# LTC6803.net
KiCad netlist of a schematic drawn in Altium Designer
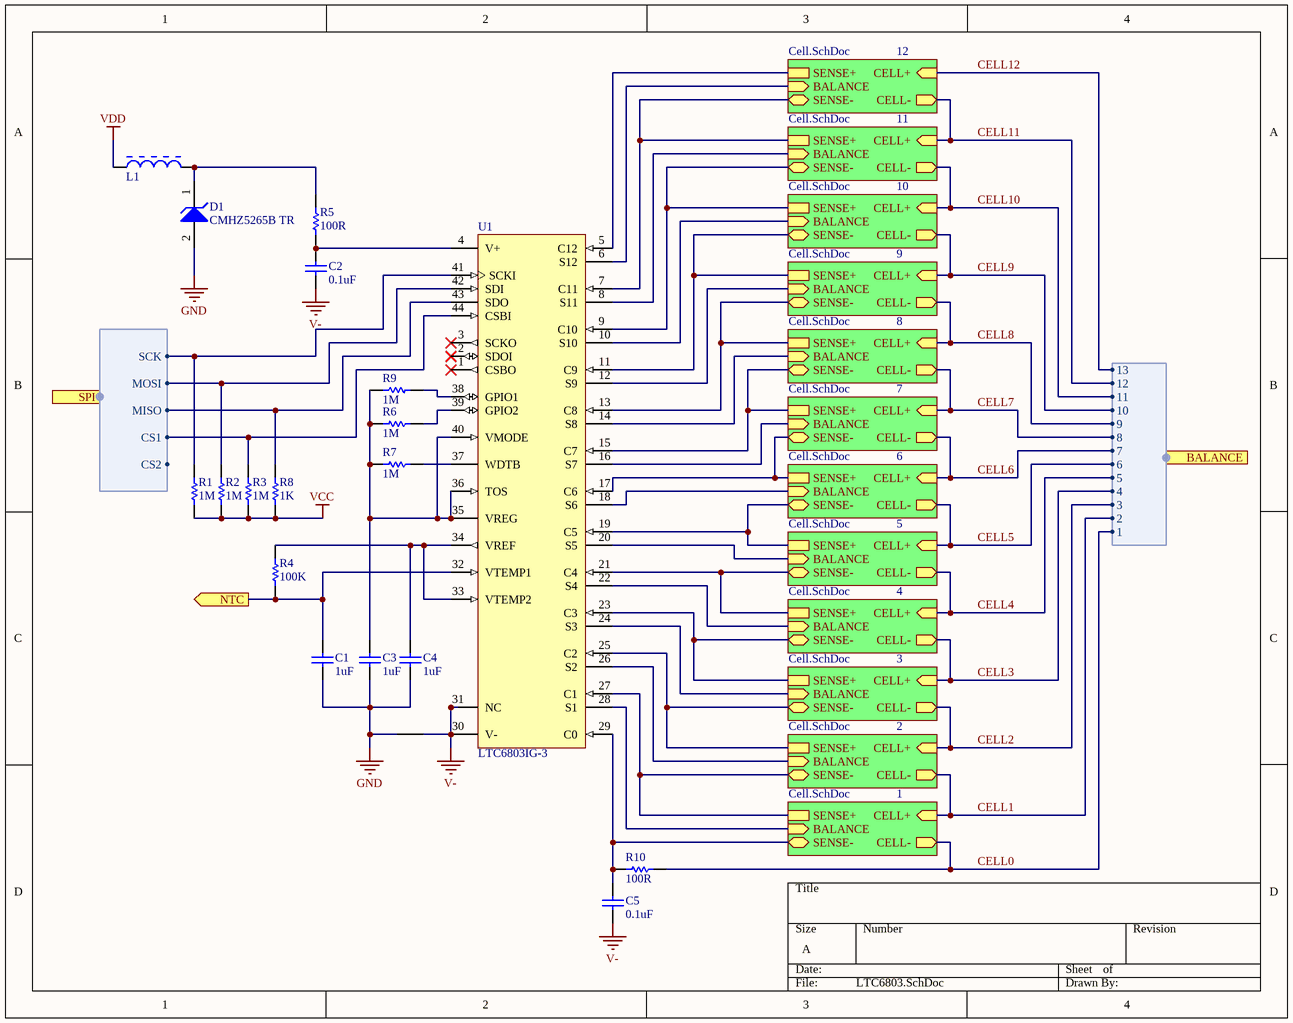
[diagram p0: LTC6803.SchDoc]

(export (version "E")
  (design (tool "Eeschema 10.0.6"))
  (components
    (comp (ref "*") (value "NetTie") (footprint "NetTie") (libsource (lib "Components") (part "NetTie")))
    (comp (ref "C1")
      (value "1uF")
      (footprint "C0603[1608X92]")
      (description "1uF 6.3V 10% 0603 (1608 Metric)")
      (fields (field (name "PARTNUMBER") "GRM188R60J105KA01D") (field (name "MANUFACTURER") "Murata"))
      (libsource (lib "Capacitors") (part "CAP_1uF_6.3V_0603_10%"))
    )
    (comp (ref "C2")
      (value "0.1uF")
      (footprint "C0603[1608X92]")
      (description "0.1uF 100V 10% 0603 (1608 Metric)")
      (fields (field (name "PARTNUMBER") "GRM188R72A104KA35D") (field (name "MANUFACTURER") "Murata"))
      (libsource (lib "Capacitors") (part "CAP_0.1uF_100V_0603_10%"))
    )
    (comp (ref "C3")
      (value "1uF")
      (footprint "C0603[1608X92]")
      (description "1uF 6.3V 10% 0603 (1608 Metric)")
      (fields (field (name "PARTNUMBER") "GRM188R60J105KA01D") (field (name "MANUFACTURER") "Murata"))
      (libsource (lib "Capacitors") (part "CAP_1uF_6.3V_0603_10%"))
    )
    (comp (ref "C4")
      (value "1uF")
      (footprint "C0603[1608X92]")
      (description "1uF 6.3V 10% 0603 (1608 Metric)")
      (fields (field (name "PARTNUMBER") "GRM188R60J105KA01D") (field (name "MANUFACTURER") "Murata"))
      (libsource (lib "Capacitors") (part "CAP_1uF_6.3V_0603_10%"))
    )
    (comp (ref "C5")
      (value "0.1uF")
      (footprint "C0603[1608X92]")
      (description "0.1uF 6.3V 10% 0603 (1608 Metric)")
      (fields (field (name "PARTNUMBER") "GRM188R70J104KA01D") (field (name "MANUFACTURER") "Murata"))
      (libsource (lib "Capacitors") (part "CAP_0.1uF_6.3V_0603_10%"))
    )
    (comp (ref "D1")
      (value "CMHZ5265B TR")
      (footprint "SOD-123")
      (description "Zener Diodes 500mW Zener Diode 185mA 58.9V to 2V")
      (fields (field (name "PARTNUMBER") "CMHZ5265B") (field (name "MANUFACTURER") "Central Semiconductor"))
      (libsource (lib "Diodes") (part "CMHZ5265B"))
    )
    (comp (ref "L1")
      (value "MURA-FB-2")
      (footprint "MURA-BLM31-B60-CHIP-2_V3")
      (description "EMI Filter Beads, Chips & Arrays 1206 33 OHM")
      (fields (field (name "PARTNUMBER") "BLM31PG330SN1L") (field (name "MANUFACTURER") "Murata"))
      (libsource (lib "Components") (part "MURA-FB-2"))
    )
    (comp (ref "R1")
      (value "1M")
      (footprint "R0603[1608]")
      (description "1M 0.25W 1% 0603 (1005 Metric)")
      (fields (field (name "MANUFACTURER") "Vishay / Dale") (field (name "PARTNUMBER") "CRCW06031M00JNEAHP"))
      (libsource (lib "Resistors") (part "RES_1M_0603_1%"))
    )
    (comp (ref "R2")
      (value "1M")
      (footprint "R0603[1608]")
      (description "1M 0.25W 1% 0603 (1005 Metric)")
      (fields (field (name "MANUFACTURER") "Vishay / Dale") (field (name "PARTNUMBER") "CRCW06031M00JNEAHP"))
      (libsource (lib "Resistors") (part "RES_1M_0603_1%"))
    )
    (comp (ref "R3")
      (value "1M")
      (footprint "R0603[1608]")
      (description "1M 0.25W 1% 0603 (1005 Metric)")
      (fields (field (name "MANUFACTURER") "Vishay / Dale") (field (name "PARTNUMBER") "CRCW06031M00JNEAHP"))
      (libsource (lib "Resistors") (part "RES_1M_0603_1%"))
    )
    (comp (ref "R4")
      (value "100K")
      (footprint "R0603[1608]")
      (description "100K 0.25W 1% 0603 (1005 Metric)")
      (fields (field (name "MANUFACTURER") "Vishay / Dale") (field (name "PARTNUMBER") "CRCW0603100KFKEAHP"))
      (libsource (lib "Resistors") (part "RES_100K_0603_1%"))
    )
    (comp (ref "R5")
      (value "100R")
      (footprint "R0603[1608]")
      (description "100R 0.25W 1% 0603 (1005 Metric)")
      (fields (field (name "MANUFACTURER") "Vishay / Dale") (field (name "PARTNUMBER") "CRCW0603100RFKEAHP"))
      (libsource (lib "Resistors") (part "RES_100R_0603_1%"))
    )
    (comp (ref "R6")
      (value "1M")
      (footprint "R0603[1608]")
      (description "1M 0.25W 1% 0603 (1005 Metric)")
      (fields (field (name "MANUFACTURER") "Vishay / Dale") (field (name "PARTNUMBER") "CRCW06031M00JNEAHP"))
      (libsource (lib "Resistors") (part "RES_1M_0603_1%"))
    )
    (comp (ref "R7")
      (value "1M")
      (footprint "R0603[1608]")
      (description "1M 0.25W 1% 0603 (1005 Metric)")
      (fields (field (name "MANUFACTURER") "Vishay / Dale") (field (name "PARTNUMBER") "CRCW06031M00JNEAHP"))
      (libsource (lib "Resistors") (part "RES_1M_0603_1%"))
    )
    (comp (ref "R8")
      (value "1K")
      (footprint "R0603[1608]")
      (description "1K 0.25W 1% 0603 (1005 Metric)")
      (fields (field (name "MANUFACTURER") "Vishay / Dale") (field (name "PARTNUMBER") "CRCW06031K00FKEAHP"))
      (libsource (lib "Resistors") (part "RES_1K_0603_1%"))
    )
    (comp (ref "R9")
      (value "1M")
      (footprint "R0603[1608]")
      (description "1M 0.25W 1% 0603 (1005 Metric)")
      (fields (field (name "MANUFACTURER") "Vishay / Dale") (field (name "PARTNUMBER") "CRCW06031M00JNEAHP"))
      (libsource (lib "Resistors") (part "RES_1M_0603_1%"))
    )
    (comp (ref "R10")
      (value "100R")
      (footprint "R0603[1608]")
      (description "100R 0.25W 1% 0603 (1005 Metric)")
      (fields (field (name "MANUFACTURER") "Vishay / Dale") (field (name "PARTNUMBER") "CRCW0603100RFKEAHP"))
      (libsource (lib "Resistors") (part "RES_100R_0603_1%"))
    )
    (comp (ref "U1")
      (value "LTC6803IG-3")
      (footprint "TSSOP-44")
      (fields (field (name "PARTNUMBER") "LTC6803IG-3#PBF") (field (name "MANUFACTURER") "Linear Technology"))
      (libsource (lib "ICs") (part "LTC6803IG-3"))
    )
  )
  (nets
    (net (code "3") (name "/BALANCE") (class "Default")
      (node (ref "U1") (pin "28") (pinfunction "S1_28") (pintype "tri_state"))
    )
    (net (code "4") (name "/BALANCE_1") (class "Default")
      (node (ref "U1") (pin "10") (pinfunction "S10_10") (pintype "tri_state"))
    )
    (net (code "5") (name "/BALANCE_2") (class "Default")
      (node (ref "U1") (pin "6") (pinfunction "S12_6") (pintype "tri_state"))
    )
    (net (code "6") (name "/BALANCE_3") (class "Default")
      (node (ref "U1") (pin "8") (pinfunction "S11_8") (pintype "tri_state"))
    )
    (net (code "7") (name "/BALANCE_4") (class "Default")
      (node (ref "U1") (pin "12") (pinfunction "S9_12") (pintype "tri_state"))
    )
    (net (code "8") (name "/BALANCE_5") (class "Default")
      (node (ref "U1") (pin "14") (pinfunction "S8_14") (pintype "tri_state"))
    )
    (net (code "9") (name "/BALANCE_6") (class "Default")
      (node (ref "U1") (pin "16") (pinfunction "S7_16") (pintype "tri_state"))
    )
    (net (code "10") (name "/BALANCE_7") (class "Default")
      (node (ref "U1") (pin "18") (pinfunction "S6_18") (pintype "tri_state"))
    )
    (net (code "11") (name "/BALANCE_8") (class "Default")
      (node (ref "U1") (pin "20") (pinfunction "S5_20") (pintype "tri_state"))
    )
    (net (code "12") (name "/BALANCE_9") (class "Default")
      (node (ref "U1") (pin "22") (pinfunction "S4_22") (pintype "tri_state"))
    )
    (net (code "13") (name "/BALANCE_10") (class "Default")
      (node (ref "U1") (pin "24") (pinfunction "S3_24") (pintype "tri_state"))
    )
    (net (code "14") (name "/BALANCE_11") (class "Default")
      (node (ref "U1") (pin "26") (pinfunction "S2_26") (pintype "tri_state"))
    )
    (net (code "15") (name "/CELL0") (class "Default")
      (node (ref "R10") (pin "1") (pinfunction "1_1") (pintype "passive"))
    )
    (net (code "28") (name "/NTC") (class "Default")
      (node (ref "C1") (pin "2") (pinfunction "2_2") (pintype "passive"))
      (node (ref "R4") (pin "1") (pinfunction "1_1") (pintype "passive"))
      (node (ref "U1") (pin "32") (pinfunction "VTEMP1_32") (pintype "input"))
    )
    (net (code "29") (name "/SENSE+") (class "Default")
      (node (ref "U1") (pin "27") (pinfunction "C1_27") (pintype "input"))
    )
    (net (code "30") (name "/SENSE+_1") (class "Default")
      (node (ref "U1") (pin "9") (pinfunction "C10_9") (pintype "input"))
    )
    (net (code "31") (name "/SENSE+_2") (class "Default")
      (node (ref "U1") (pin "11") (pinfunction "C9_11") (pintype "input"))
    )
    (net (code "32") (name "/SENSE+_3") (class "Default")
      (node (ref "U1") (pin "13") (pinfunction "C8_13") (pintype "input"))
    )
    (net (code "33") (name "/SENSE+_4") (class "Default")
      (node (ref "U1") (pin "7") (pinfunction "C11_7") (pintype "input"))
    )
    (net (code "34") (name "/SENSE+_5") (class "Default")
      (node (ref "U1") (pin "5") (pinfunction "C12_5") (pintype "input"))
    )
    (net (code "35") (name "/SENSE+_6") (class "Default")
      (node (ref "U1") (pin "15") (pinfunction "C7_15") (pintype "input"))
    )
    (net (code "36") (name "/SENSE+_7") (class "Default")
      (node (ref "U1") (pin "17") (pinfunction "C6_17") (pintype "input"))
    )
    (net (code "37") (name "/SENSE+_8") (class "Default")
      (node (ref "U1") (pin "19") (pinfunction "C5_19") (pintype "input"))
    )
    (net (code "38") (name "/SENSE+_9") (class "Default")
      (node (ref "U1") (pin "21") (pinfunction "C4_21") (pintype "input"))
    )
    (net (code "39") (name "/SENSE+_10") (class "Default")
      (node (ref "U1") (pin "23") (pinfunction "C3_23") (pintype "input"))
    )
    (net (code "40") (name "/SENSE+_11") (class "Default")
      (node (ref "U1") (pin "25") (pinfunction "C2_25") (pintype "input"))
    )
    (net (code "41") (name "/SENSE-") (class "Default")
      (node (ref "C5") (pin "2") (pinfunction "2_2") (pintype "passive"))
      (node (ref "R10") (pin "2") (pinfunction "2_2") (pintype "passive"))
      (node (ref "U1") (pin "29") (pinfunction "C0_29") (pintype "input"))
    )
    (net (code "44") (name "GND") (class "Default")
      (node (ref "*") (pin "1") (pinfunction "1_1") (pintype "passive"))
      (node (ref "C1") (pin "1") (pinfunction "1_1") (pintype "passive"))
      (node (ref "C3") (pin "1") (pinfunction "1_1") (pintype "passive"))
      (node (ref "C4") (pin "1") (pinfunction "1_1") (pintype "passive"))
      (node (ref "D1") (pin "2") (pinfunction "A_2") (pintype "passive"))
    )
    (net (code "45") (name "Net-(D1-K)") (class "Default")
      (node (ref "D1") (pin "1") (pinfunction "K_1") (pintype "passive"))
      (node (ref "L1") (pin "2") (pinfunction "2_2") (pintype "passive"))
      (node (ref "R5") (pin "2") (pinfunction "2_2") (pintype "passive"))
    )
    (net (code "46") (name "Net-(U1-CSBI)") (class "Default")
      (node (ref "R3") (pin "2") (pinfunction "2_2") (pintype "passive"))
      (node (ref "U1") (pin "44") (pinfunction "CSBI_44") (pintype "input"))
    )
    (net (code "47") (name "Net-(U1-GPIO1)") (class "Default")
      (node (ref "R9") (pin "1") (pinfunction "1_1") (pintype "passive"))
      (node (ref "U1") (pin "38") (pinfunction "GPIO1_38") (pintype "bidirectional"))
    )
    (net (code "48") (name "Net-(U1-GPIO2)") (class "Default")
      (node (ref "R6") (pin "1") (pinfunction "1_1") (pintype "passive"))
      (node (ref "U1") (pin "39") (pinfunction "GPIO2_39") (pintype "bidirectional"))
    )
    (net (code "49") (name "Net-(U1-SCKI)") (class "Default")
      (node (ref "R1") (pin "2") (pinfunction "2_2") (pintype "passive"))
      (node (ref "U1") (pin "41") (pinfunction "SCKI_41") (pintype "input"))
    )
    (net (code "50") (name "Net-(U1-SDI)") (class "Default")
      (node (ref "R2") (pin "2") (pinfunction "2_2") (pintype "passive"))
      (node (ref "U1") (pin "42") (pinfunction "SDI_42") (pintype "input"))
    )
    (net (code "51") (name "Net-(U1-SDO)") (class "Default")
      (node (ref "R8") (pin "2") (pinfunction "2_2") (pintype "passive"))
      (node (ref "U1") (pin "43") (pinfunction "SDO_43") (pintype "open_collector"))
    )
    (net (code "52") (name "Net-(U1-TOS)") (class "Default")
      (node (ref "C3") (pin "2") (pinfunction "2_2") (pintype "passive"))
      (node (ref "R6") (pin "2") (pinfunction "2_2") (pintype "passive"))
      (node (ref "R7") (pin "2") (pinfunction "2_2") (pintype "passive"))
      (node (ref "R9") (pin "2") (pinfunction "2_2") (pintype "passive"))
      (node (ref "U1") (pin "35") (pinfunction "VREG_35") (pintype "power_in"))
      (node (ref "U1") (pin "36") (pinfunction "TOS_36") (pintype "input"))
      (node (ref "U1") (pin "40") (pinfunction "VMODE_40") (pintype "input"))
    )
    (net (code "53") (name "Net-(U1-V+)") (class "Default")
      (node (ref "C2") (pin "2") (pinfunction "2_2") (pintype "passive"))
      (node (ref "R5") (pin "1") (pinfunction "1_1") (pintype "passive"))
      (node (ref "U1") (pin "4") (pinfunction "V+_4") (pintype "power_in"))
    )
    (net (code "54") (name "Net-(U1-VREF)") (class "Default")
      (node (ref "C4") (pin "2") (pinfunction "2_2") (pintype "passive"))
      (node (ref "R4") (pin "2") (pinfunction "2_2") (pintype "passive"))
      (node (ref "U1") (pin "33") (pinfunction "VTEMP2_33") (pintype "input"))
      (node (ref "U1") (pin "34") (pinfunction "VREF_34") (pintype "output"))
    )
    (net (code "55") (name "Net-(U1-WDTB)") (class "Default")
      (node (ref "R7") (pin "1") (pinfunction "1_1") (pintype "passive"))
      (node (ref "U1") (pin "37") (pinfunction "WDTB_37") (pintype "open_collector"))
    )
    (net (code "56") (name "V-") (class "Default")
      (node (ref "*") (pin "2") (pinfunction "2_2") (pintype "passive"))
      (node (ref "C2") (pin "1") (pinfunction "1_1") (pintype "passive"))
      (node (ref "C5") (pin "1") (pinfunction "1_1") (pintype "passive"))
      (node (ref "U1") (pin "30") (pinfunction "V-_30") (pintype "power_in"))
      (node (ref "U1") (pin "31") (pinfunction "NC_31") (pintype "passive"))
    )
    (net (code "57") (name "VCC") (class "Default")
      (node (ref "R1") (pin "1") (pinfunction "1_1") (pintype "passive"))
      (node (ref "R2") (pin "1") (pinfunction "1_1") (pintype "passive"))
      (node (ref "R3") (pin "1") (pinfunction "1_1") (pintype "passive"))
      (node (ref "R8") (pin "1") (pinfunction "1_1") (pintype "passive"))
    )
    (net (code "58") (name "VDD") (class "Default")
      (node (ref "L1") (pin "1") (pinfunction "1_1") (pintype "passive"))
    )
    (net (code "59") (name "unconnected-(U1-CSBO-Pad1)") (class "Default")
      (node (ref "U1") (pin "1") (pinfunction "CSBO_1") (pintype "output+no_connect"))
    )
    (net (code "60") (name "unconnected-(U1-SCKO-Pad3)") (class "Default")
      (node (ref "U1") (pin "3") (pinfunction "SCKO_3") (pintype "output+no_connect"))
    )
    (net (code "61") (name "unconnected-(U1-SDOI-Pad2)") (class "Default")
      (node (ref "U1") (pin "2") (pinfunction "SDOI_2") (pintype "bidirectional+no_connect"))
    )
  )
)
